# Voltage_Divider.net
KiCad netlist of a schematic drawn in EAGLE
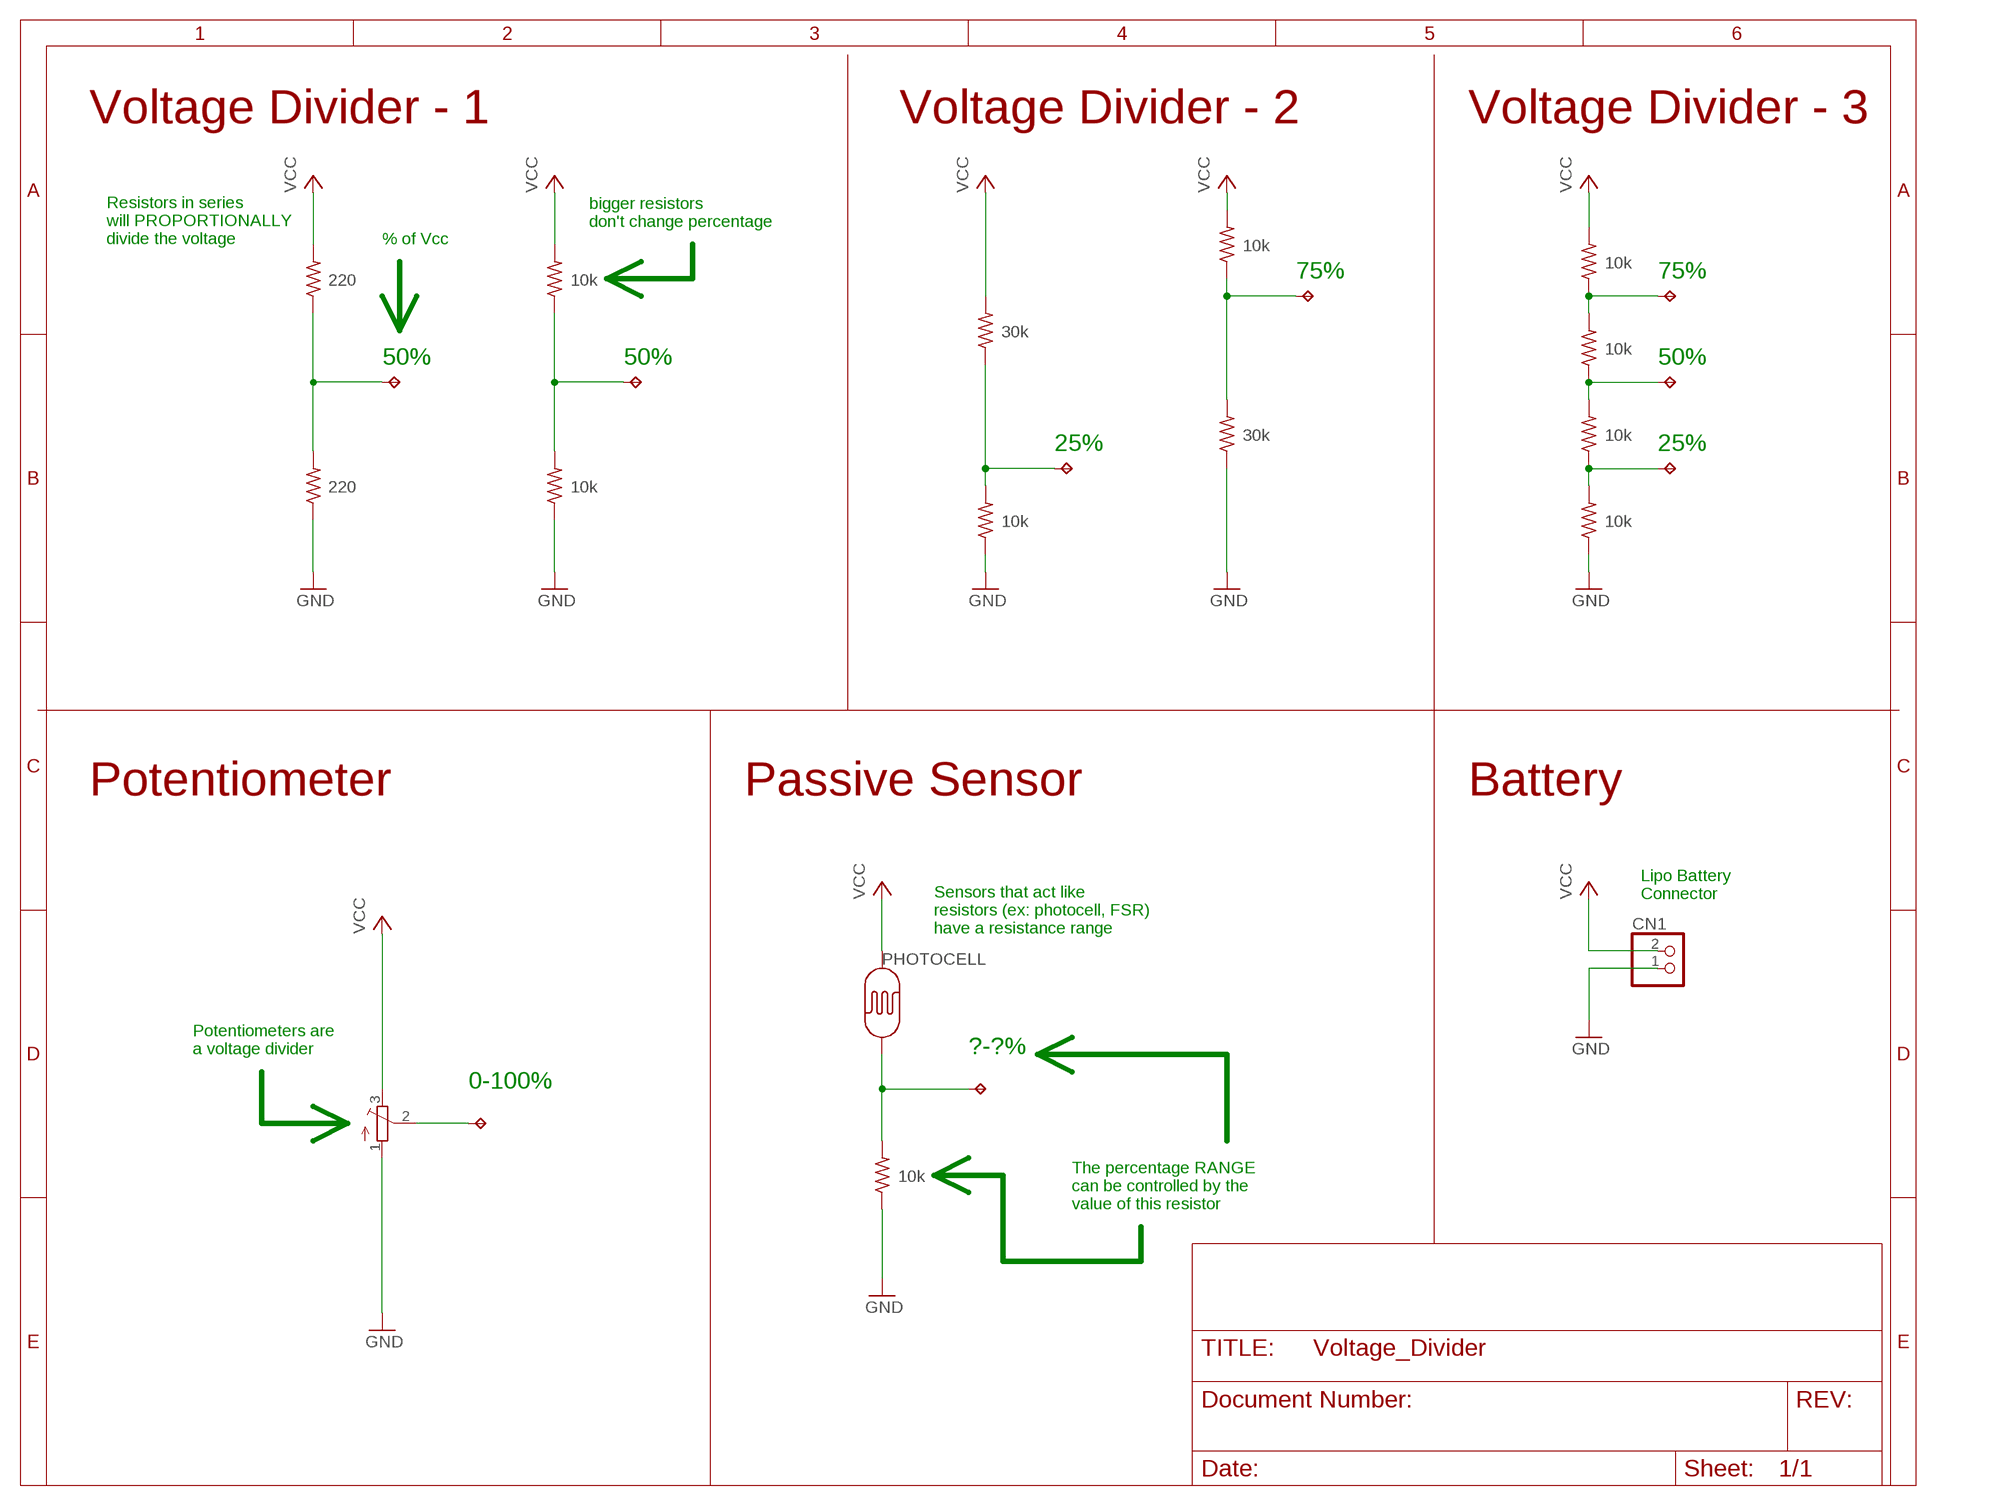
[diagram p0: schematic, sheet 1]

(export (version "E")
  (design (tool "Eeschema 10.0.6"))
  (components
    (comp (ref "CN1")
      (value "JST_2PIN-SMT-RA")
      (footprint "eagle-import:JST-PH-2-SMT-RA")
      (libsource (lib "eagle-import") (part "JST_2PIN-SMT-RA"))
    )
    (comp (ref "PHOTOCELL")
      (value "PHOTOCELLPTH")
      (footprint "eagle-import:PHOTOCELL")
      (libsource (lib "eagle-import") (part "PHOTOCELLPTH"))
    )
    (comp (ref "R1")
      (value "220")
      (footprint "eagle-import:R0603")
      (libsource (lib "eagle-import") (part "R-US_R0603"))
    )
    (comp (ref "R2")
      (value "220")
      (footprint "eagle-import:R0603")
      (libsource (lib "eagle-import") (part "R-US_R0603"))
    )
    (comp (ref "R3")
      (value "10k")
      (footprint "eagle-import:R0603")
      (libsource (lib "eagle-import") (part "R-US_R0603"))
    )
    (comp (ref "R4")
      (value "10k")
      (footprint "eagle-import:R0603")
      (libsource (lib "eagle-import") (part "R-US_R0603"))
    )
    (comp (ref "R5")
      (value "30k")
      (footprint "eagle-import:R0603")
      (libsource (lib "eagle-import") (part "R-US_R0603"))
    )
    (comp (ref "R6")
      (value "10k")
      (footprint "eagle-import:R0603")
      (libsource (lib "eagle-import") (part "R-US_R0603"))
    )
    (comp (ref "R7")
      (value "10k")
      (footprint "eagle-import:R0603")
      (libsource (lib "eagle-import") (part "R-US_R0603"))
    )
    (comp (ref "R8")
      (value "30k")
      (footprint "eagle-import:R0603")
      (libsource (lib "eagle-import") (part "R-US_R0603"))
    )
    (comp (ref "R9")
      (value "10k")
      (footprint "eagle-import:R0603")
      (libsource (lib "eagle-import") (part "R-US_R0603"))
    )
    (comp (ref "R10")
      (value "10k")
      (footprint "eagle-import:R0603")
      (libsource (lib "eagle-import") (part "R-US_R0603"))
    )
    (comp (ref "R11")
      (value "10k")
      (footprint "eagle-import:R0603")
      (libsource (lib "eagle-import") (part "R-US_R0603"))
    )
    (comp (ref "R12")
      (value "10k")
      (footprint "eagle-import:R0603")
      (libsource (lib "eagle-import") (part "R-US_R0603"))
    )
    (comp (ref "R14")
      (value "10k")
      (footprint "eagle-import:R0603")
      (libsource (lib "eagle-import") (part "R-US_R0603"))
    )
    (comp (ref "TM1")
      (value "TRIMPOTTC33X")
      (footprint "eagle-import:TC33X")
      (libsource (lib "eagle-import") (part "TRIMPOTTC33X"))
    )
    (comp (ref "TP1")
      (value "TPTP20R")
      (footprint "eagle-import:TP20R")
      (libsource (lib "eagle-import") (part "TPTP20R"))
    )
    (comp (ref "TP2")
      (value "TPTP20R")
      (footprint "eagle-import:TP20R")
      (libsource (lib "eagle-import") (part "TPTP20R"))
    )
    (comp (ref "TP3")
      (value "TPTP20R")
      (footprint "eagle-import:TP20R")
      (libsource (lib "eagle-import") (part "TPTP20R"))
    )
    (comp (ref "TP4")
      (value "TPTP20R")
      (footprint "eagle-import:TP20R")
      (libsource (lib "eagle-import") (part "TPTP20R"))
    )
    (comp (ref "TP5")
      (value "TPTP20R")
      (footprint "eagle-import:TP20R")
      (libsource (lib "eagle-import") (part "TPTP20R"))
    )
    (comp (ref "TP6")
      (value "TPTP20R")
      (footprint "eagle-import:TP20R")
      (libsource (lib "eagle-import") (part "TPTP20R"))
    )
    (comp (ref "TP7")
      (value "TPTP20R")
      (footprint "eagle-import:TP20R")
      (libsource (lib "eagle-import") (part "TPTP20R"))
    )
    (comp (ref "TP8")
      (value "TPTP20R")
      (footprint "eagle-import:TP20R")
      (libsource (lib "eagle-import") (part "TPTP20R"))
    )
    (comp (ref "TP9")
      (value "TPTP20R")
      (footprint "eagle-import:TP20R")
      (libsource (lib "eagle-import") (part "TPTP20R"))
    )
  )
  (nets
    (net (code "2") (name "GND") (class "Default")
      (node (ref "CN1") (pin "1") (pinfunction "2_1") (pintype "passive"))
      (node (ref "R12") (pin "1") (pinfunction "1_1") (pintype "passive"))
      (node (ref "R14") (pin "1") (pinfunction "1_1") (pintype "passive"))
      (node (ref "R2") (pin "1") (pinfunction "1_1") (pintype "passive"))
      (node (ref "R4") (pin "1") (pinfunction "1_1") (pintype "passive"))
      (node (ref "R6") (pin "1") (pinfunction "1_1") (pintype "passive"))
      (node (ref "R8") (pin "1") (pinfunction "1_1") (pintype "passive"))
      (node (ref "TM1") (pin "1") (pinfunction "A_1") (pintype "passive"))
    )
    (net (code "3") (name "Net-(PHOTOCELL-P$1)") (class "Default")
      (node (ref "PHOTOCELL") (pin "1") (pinfunction "P$1_1") (pintype "bidirectional"))
      (node (ref "R14") (pin "2") (pinfunction "2_2") (pintype "passive"))
      (node (ref "TP9") (pin "TP") (pinfunction "TP_TP") (pintype "input"))
    )
    (net (code "4") (name "Net-(R1-Pad1)") (class "Default")
      (node (ref "R1") (pin "1") (pinfunction "1_1") (pintype "passive"))
      (node (ref "R2") (pin "2") (pinfunction "2_2") (pintype "passive"))
      (node (ref "TP1") (pin "TP") (pinfunction "TP_TP") (pintype "input"))
    )
    (net (code "5") (name "Net-(R3-Pad1)") (class "Default")
      (node (ref "R3") (pin "1") (pinfunction "1_1") (pintype "passive"))
      (node (ref "R4") (pin "2") (pinfunction "2_2") (pintype "passive"))
      (node (ref "TP2") (pin "TP") (pinfunction "TP_TP") (pintype "input"))
    )
    (net (code "6") (name "Net-(R5-Pad1)") (class "Default")
      (node (ref "R5") (pin "1") (pinfunction "1_1") (pintype "passive"))
      (node (ref "R6") (pin "2") (pinfunction "2_2") (pintype "passive"))
      (node (ref "TP3") (pin "TP") (pinfunction "TP_TP") (pintype "input"))
    )
    (net (code "7") (name "Net-(R7-Pad1)") (class "Default")
      (node (ref "R7") (pin "1") (pinfunction "1_1") (pintype "passive"))
      (node (ref "R8") (pin "2") (pinfunction "2_2") (pintype "passive"))
      (node (ref "TP4") (pin "TP") (pinfunction "TP_TP") (pintype "input"))
    )
    (net (code "8") (name "Net-(R10-Pad1)") (class "Default")
      (node (ref "R10") (pin "1") (pinfunction "1_1") (pintype "passive"))
      (node (ref "R11") (pin "2") (pinfunction "2_2") (pintype "passive"))
      (node (ref "TP7") (pin "TP") (pinfunction "TP_TP") (pintype "input"))
    )
    (net (code "9") (name "Net-(R10-Pad2)") (class "Default")
      (node (ref "R10") (pin "2") (pinfunction "2_2") (pintype "passive"))
      (node (ref "R9") (pin "1") (pinfunction "1_1") (pintype "passive"))
      (node (ref "TP6") (pin "TP") (pinfunction "TP_TP") (pintype "input"))
    )
    (net (code "10") (name "Net-(R11-Pad1)") (class "Default")
      (node (ref "R11") (pin "1") (pinfunction "1_1") (pintype "passive"))
      (node (ref "R12") (pin "2") (pinfunction "2_2") (pintype "passive"))
      (node (ref "TP8") (pin "TP") (pinfunction "TP_TP") (pintype "input"))
    )
    (net (code "11") (name "Net-(TM1-S)") (class "Default")
      (node (ref "TM1") (pin "2") (pinfunction "S_2") (pintype "passive"))
      (node (ref "TP5") (pin "TP") (pinfunction "TP_TP") (pintype "input"))
    )
    (net (code "12") (name "VCC") (class "Default")
      (node (ref "CN1") (pin "2") (pinfunction "1_2") (pintype "passive"))
      (node (ref "PHOTOCELL") (pin "2") (pinfunction "P$2_2") (pintype "bidirectional"))
      (node (ref "R1") (pin "2") (pinfunction "2_2") (pintype "passive"))
      (node (ref "R3") (pin "2") (pinfunction "2_2") (pintype "passive"))
      (node (ref "R5") (pin "2") (pinfunction "2_2") (pintype "passive"))
      (node (ref "R7") (pin "2") (pinfunction "2_2") (pintype "passive"))
      (node (ref "R9") (pin "2") (pinfunction "2_2") (pintype "passive"))
      (node (ref "TM1") (pin "3") (pinfunction "E_3") (pintype "passive"))
    )
  )
)
